# ahcp.net
KiCad netlist of a schematic drawn in EAGLE
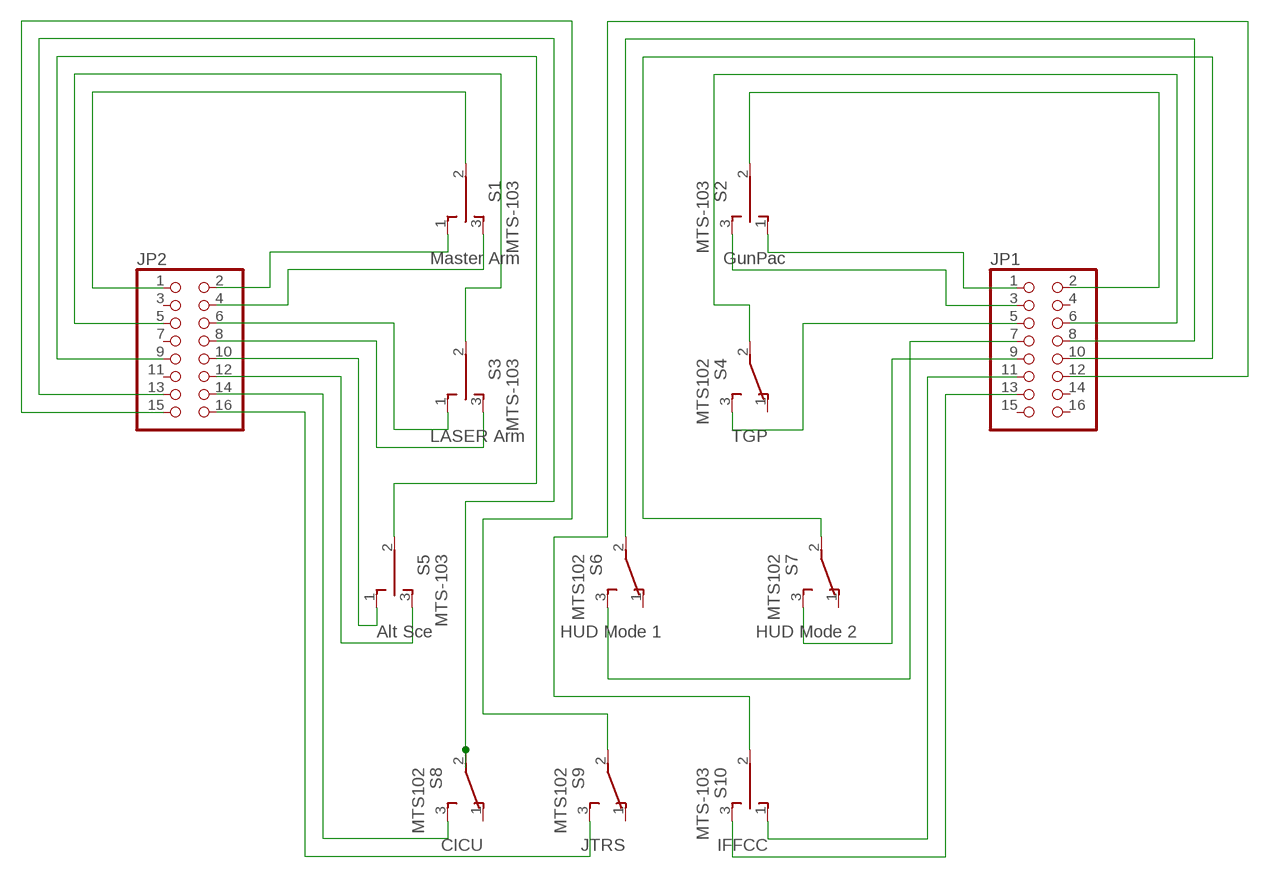
[diagram p0: schematic, sheet 1]

(export (version "E")
  (design (tool "Eeschema 10.0.6"))
  (components
    (comp (ref "JP1")
      (value "PINHD-2X8")
      (footprint "eagle-import:2X08")
      (libsource (lib "eagle-import") (part "PINHD-2X8"))
    )
    (comp (ref "JP2")
      (value "PINHD-2X8")
      (footprint "eagle-import:2X08")
      (libsource (lib "eagle-import") (part "PINHD-2X8"))
    )
    (comp (ref "S1")
      (value "MTS-103")
      (footprint "eagle-import:TL3XPO")
      (fields (field (name "A10") "Master Arm"))
      (libsource (lib "eagle-import") (part "TL39PO"))
    )
    (comp (ref "S2")
      (value "MTS-103")
      (footprint "eagle-import:TL3XPO")
      (fields (field (name "A10") "GunPac"))
      (libsource (lib "eagle-import") (part "TL39PO"))
    )
    (comp (ref "S3")
      (value "MTS-103")
      (footprint "eagle-import:TL3XPO")
      (fields (field (name "A10") "LASER Arm"))
      (libsource (lib "eagle-import") (part "TL39PO"))
    )
    (comp (ref "S4")
      (value "MTS102")
      (footprint "eagle-import:TL3XPO")
      (fields (field (name "A10") "TGP"))
      (libsource (lib "eagle-import") (part "TL36PO"))
    )
    (comp (ref "S5")
      (value "MTS-103")
      (footprint "eagle-import:TL3XPO")
      (fields (field (name "A10") "Alt Sce"))
      (libsource (lib "eagle-import") (part "TL39PO"))
    )
    (comp (ref "S6")
      (value "MTS102")
      (footprint "eagle-import:TL3XPO")
      (fields (field (name "A10") "HUD Mode 1"))
      (libsource (lib "eagle-import") (part "TL36PO"))
    )
    (comp (ref "S7")
      (value "MTS102")
      (footprint "eagle-import:TL3XPO")
      (fields (field (name "A10") "HUD Mode 2"))
      (libsource (lib "eagle-import") (part "TL36PO"))
    )
    (comp (ref "S8")
      (value "MTS102")
      (footprint "eagle-import:TL3XPO")
      (fields (field (name "A10") "CICU"))
      (libsource (lib "eagle-import") (part "TL36PO"))
    )
    (comp (ref "S9")
      (value "MTS102")
      (footprint "eagle-import:TL3XPO")
      (fields (field (name "A10") "JTRS"))
      (libsource (lib "eagle-import") (part "TL36PO"))
    )
    (comp (ref "S10")
      (value "MTS-103")
      (footprint "eagle-import:TL3XPO")
      (fields (field (name "A10") "IFFCC"))
      (libsource (lib "eagle-import") (part "TL39PO"))
    )
  )
  (nets
    (net (code "1") (name "Net-(S1-O)") (class "Default")
      (node (ref "JP2") (pin "2") (pinfunction "2_2") (pintype "passive"))
      (node (ref "S1") (pin "1") (pinfunction "O_1") (pintype "passive"))
    )
    (net (code "2") (name "Net-(S1-P)") (class "Default")
      (node (ref "JP2") (pin "1") (pinfunction "1_1") (pintype "passive"))
      (node (ref "S1") (pin "2") (pinfunction "P_2") (pintype "passive"))
    )
    (net (code "3") (name "Net-(S1-S)") (class "Default")
      (node (ref "JP2") (pin "4") (pinfunction "4_4") (pintype "passive"))
      (node (ref "S1") (pin "3") (pinfunction "S_3") (pintype "passive"))
    )
    (net (code "4") (name "Net-(S2-O)") (class "Default")
      (node (ref "JP1") (pin "1") (pinfunction "1_1") (pintype "passive"))
      (node (ref "S2") (pin "1") (pinfunction "O_1") (pintype "passive"))
    )
    (net (code "5") (name "Net-(S2-P)") (class "Default")
      (node (ref "JP1") (pin "2") (pinfunction "2_2") (pintype "passive"))
      (node (ref "S2") (pin "2") (pinfunction "P_2") (pintype "passive"))
    )
    (net (code "6") (name "Net-(S2-S)") (class "Default")
      (node (ref "JP1") (pin "3") (pinfunction "3_3") (pintype "passive"))
      (node (ref "S2") (pin "3") (pinfunction "S_3") (pintype "passive"))
    )
    (net (code "7") (name "Net-(S3-O)") (class "Default")
      (node (ref "JP2") (pin "6") (pinfunction "6_6") (pintype "passive"))
      (node (ref "S3") (pin "1") (pinfunction "O_1") (pintype "passive"))
    )
    (net (code "8") (name "Net-(S3-P)") (class "Default")
      (node (ref "JP2") (pin "5") (pinfunction "5_5") (pintype "passive"))
      (node (ref "S3") (pin "2") (pinfunction "P_2") (pintype "passive"))
    )
    (net (code "9") (name "Net-(S3-S)") (class "Default")
      (node (ref "JP2") (pin "8") (pinfunction "8_8") (pintype "passive"))
      (node (ref "S3") (pin "3") (pinfunction "S_3") (pintype "passive"))
    )
    (net (code "10") (name "Net-(S4-P)") (class "Default")
      (node (ref "JP1") (pin "6") (pinfunction "6_6") (pintype "passive"))
      (node (ref "S4") (pin "2") (pinfunction "P_2") (pintype "passive"))
    )
    (net (code "11") (name "Net-(S4-S)") (class "Default")
      (node (ref "JP1") (pin "5") (pinfunction "5_5") (pintype "passive"))
      (node (ref "S4") (pin "3") (pinfunction "S_3") (pintype "passive"))
    )
    (net (code "12") (name "Net-(S5-O)") (class "Default")
      (node (ref "JP2") (pin "10") (pinfunction "10_10") (pintype "passive"))
      (node (ref "S5") (pin "1") (pinfunction "O_1") (pintype "passive"))
    )
    (net (code "13") (name "Net-(S5-P)") (class "Default")
      (node (ref "JP2") (pin "9") (pinfunction "9_9") (pintype "passive"))
      (node (ref "S5") (pin "2") (pinfunction "P_2") (pintype "passive"))
    )
    (net (code "14") (name "Net-(S5-S)") (class "Default")
      (node (ref "JP2") (pin "12") (pinfunction "12_12") (pintype "passive"))
      (node (ref "S5") (pin "3") (pinfunction "S_3") (pintype "passive"))
    )
    (net (code "15") (name "Net-(S6-P)") (class "Default")
      (node (ref "JP1") (pin "8") (pinfunction "8_8") (pintype "passive"))
      (node (ref "S6") (pin "2") (pinfunction "P_2") (pintype "passive"))
    )
    (net (code "16") (name "Net-(S6-S)") (class "Default")
      (node (ref "JP1") (pin "7") (pinfunction "7_7") (pintype "passive"))
      (node (ref "S6") (pin "3") (pinfunction "S_3") (pintype "passive"))
    )
    (net (code "17") (name "Net-(S7-P)") (class "Default")
      (node (ref "JP1") (pin "10") (pinfunction "10_10") (pintype "passive"))
      (node (ref "S7") (pin "2") (pinfunction "P_2") (pintype "passive"))
    )
    (net (code "18") (name "Net-(S7-S)") (class "Default")
      (node (ref "JP1") (pin "9") (pinfunction "9_9") (pintype "passive"))
      (node (ref "S7") (pin "3") (pinfunction "S_3") (pintype "passive"))
    )
    (net (code "19") (name "Net-(S8-P)") (class "Default")
      (node (ref "JP2") (pin "13") (pinfunction "13_13") (pintype "passive"))
      (node (ref "S8") (pin "2") (pinfunction "P_2") (pintype "passive"))
    )
    (net (code "20") (name "Net-(S8-S)") (class "Default")
      (node (ref "JP2") (pin "14") (pinfunction "14_14") (pintype "passive"))
      (node (ref "S8") (pin "3") (pinfunction "S_3") (pintype "passive"))
    )
    (net (code "21") (name "Net-(S9-P)") (class "Default")
      (node (ref "JP2") (pin "15") (pinfunction "15_15") (pintype "passive"))
      (node (ref "S9") (pin "2") (pinfunction "P_2") (pintype "passive"))
    )
    (net (code "22") (name "Net-(S9-S)") (class "Default")
      (node (ref "JP2") (pin "16") (pinfunction "16_16") (pintype "passive"))
      (node (ref "S9") (pin "3") (pinfunction "S_3") (pintype "passive"))
    )
    (net (code "23") (name "Net-(S10-O)") (class "Default")
      (node (ref "JP1") (pin "11") (pinfunction "11_11") (pintype "passive"))
      (node (ref "S10") (pin "1") (pinfunction "O_1") (pintype "passive"))
    )
    (net (code "24") (name "Net-(S10-P)") (class "Default")
      (node (ref "JP1") (pin "12") (pinfunction "12_12") (pintype "passive"))
      (node (ref "S10") (pin "2") (pinfunction "P_2") (pintype "passive"))
    )
    (net (code "25") (name "Net-(S10-S)") (class "Default")
      (node (ref "JP1") (pin "13") (pinfunction "13_13") (pintype "passive"))
      (node (ref "S10") (pin "3") (pinfunction "S_3") (pintype "passive"))
    )
    (net (code "26") (name "unconnected-(JP1-Pad4)") (class "Default")
      (node (ref "JP1") (pin "4") (pinfunction "4_4") (pintype "passive"))
    )
    (net (code "27") (name "unconnected-(JP1-Pad14)") (class "Default")
      (node (ref "JP1") (pin "14") (pinfunction "14_14") (pintype "passive"))
    )
    (net (code "28") (name "unconnected-(JP1-Pad15)") (class "Default")
      (node (ref "JP1") (pin "15") (pinfunction "15_15") (pintype "passive"))
    )
    (net (code "29") (name "unconnected-(JP1-Pad16)") (class "Default")
      (node (ref "JP1") (pin "16") (pinfunction "16_16") (pintype "passive"))
    )
    (net (code "30") (name "unconnected-(JP2-Pad3)") (class "Default")
      (node (ref "JP2") (pin "3") (pinfunction "3_3") (pintype "passive"))
    )
    (net (code "31") (name "unconnected-(JP2-Pad7)") (class "Default")
      (node (ref "JP2") (pin "7") (pinfunction "7_7") (pintype "passive"))
    )
    (net (code "32") (name "unconnected-(JP2-Pad11)") (class "Default")
      (node (ref "JP2") (pin "11") (pinfunction "11_11") (pintype "passive"))
    )
    (net (code "33") (name "unconnected-(S4-O-Pad1)") (class "Default")
      (node (ref "S4") (pin "1") (pinfunction "O_1") (pintype "passive"))
    )
    (net (code "34") (name "unconnected-(S6-O-Pad1)") (class "Default")
      (node (ref "S6") (pin "1") (pinfunction "O_1") (pintype "passive"))
    )
    (net (code "35") (name "unconnected-(S7-O-Pad1)") (class "Default")
      (node (ref "S7") (pin "1") (pinfunction "O_1") (pintype "passive"))
    )
    (net (code "36") (name "unconnected-(S8-O-Pad1)") (class "Default")
      (node (ref "S8") (pin "1") (pinfunction "O_1") (pintype "passive"))
    )
    (net (code "37") (name "unconnected-(S9-O-Pad1)") (class "Default")
      (node (ref "S9") (pin "1") (pinfunction "O_1") (pintype "passive"))
    )
  )
)
